# first.net
KiCad netlist of a schematic drawn in EAGLE
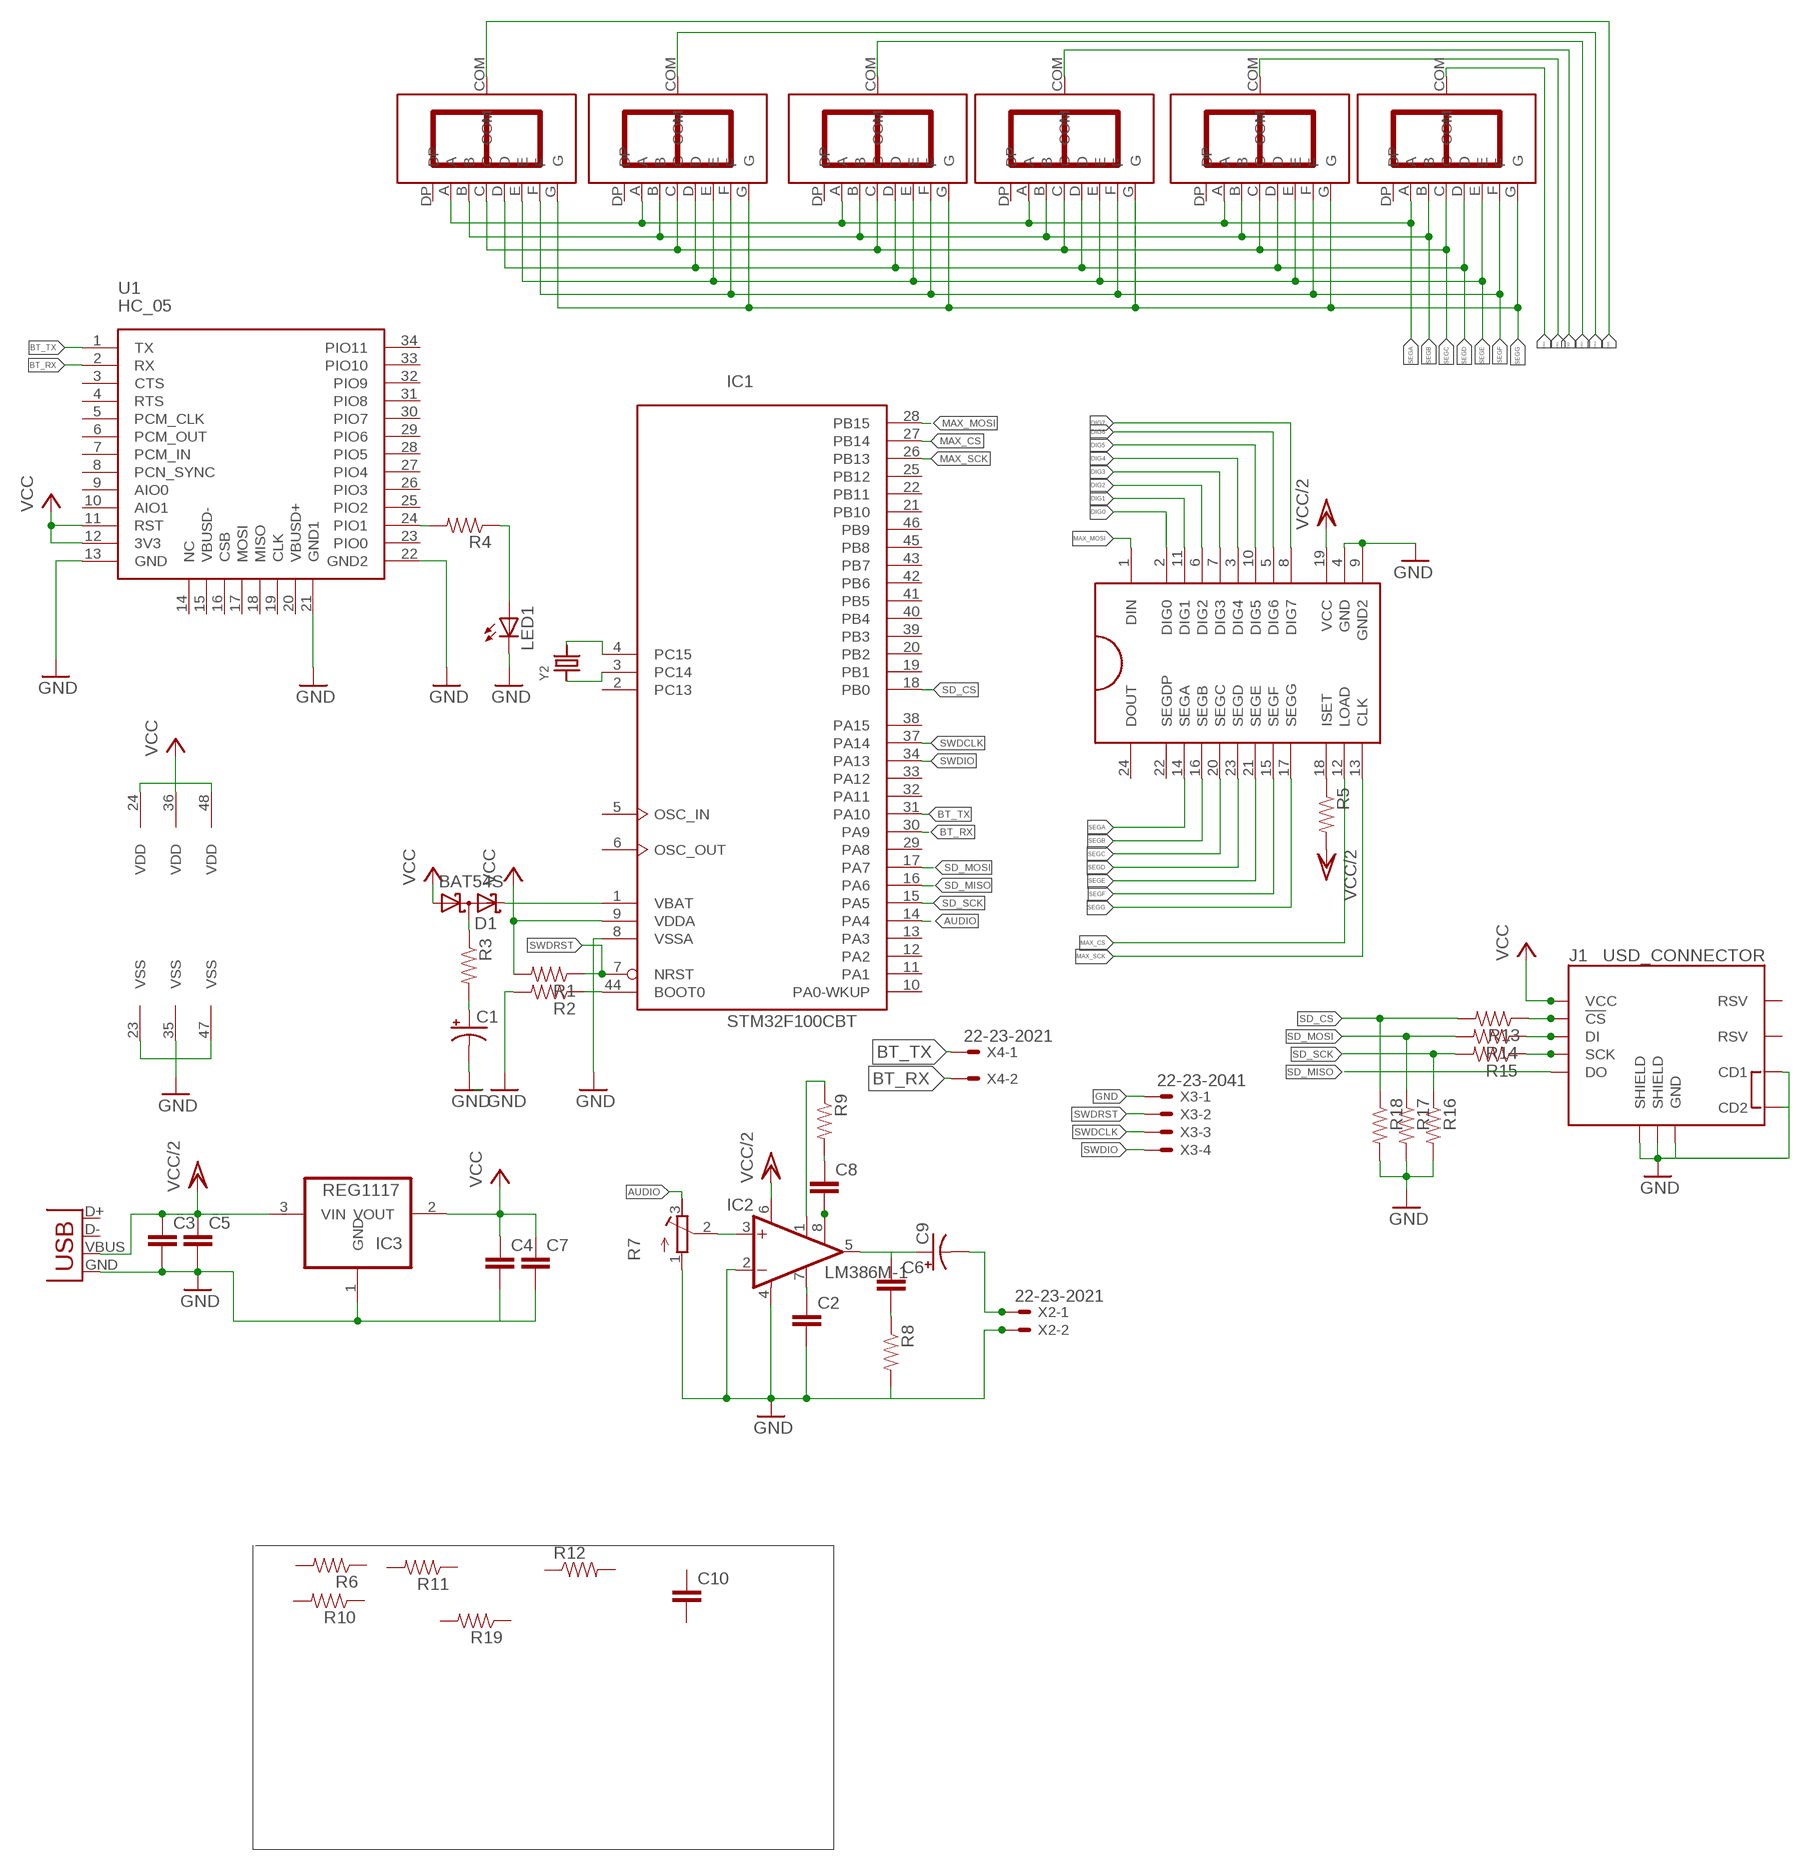
[diagram p0: schematic, sheet 1]

(export (version "E")
  (design (tool "Eeschema 10.0.6"))
  (components
    (comp (ref "C1")
      (value "CAP_POLPTH2")
      (footprint "eagle-import:CPOL-RADIAL-10UF-25V")
      (libsource (lib "eagle-import") (part "SparkFun-Passives_CAP_POLPTH2"))
    )
    (comp (ref "C2")
      (value "C-EUC0805K")
      (footprint "eagle-import:C0805K")
      (libsource (lib "eagle-import") (part "C-EUC0805K"))
    )
    (comp (ref "C3")
      (value "C-EUC0805K")
      (footprint "eagle-import:C0805K")
      (libsource (lib "eagle-import") (part "C-EUC0805K"))
    )
    (comp (ref "C4")
      (value "C-EUC0805K")
      (footprint "eagle-import:C0805K")
      (libsource (lib "eagle-import") (part "C-EUC0805K"))
    )
    (comp (ref "C5")
      (value "C-EUC0805K")
      (footprint "eagle-import:C0805K")
      (libsource (lib "eagle-import") (part "C-EUC0805K"))
    )
    (comp (ref "C6")
      (value "C-EUC0805K")
      (footprint "eagle-import:C0805K")
      (libsource (lib "eagle-import") (part "C-EUC0805K"))
    )
    (comp (ref "C7")
      (value "C-EUC0805K")
      (footprint "eagle-import:C0805K")
      (libsource (lib "eagle-import") (part "C-EUC0805K"))
    )
    (comp (ref "C8")
      (value "C-EUC0805K")
      (footprint "eagle-import:C0805K")
      (libsource (lib "eagle-import") (part "C-EUC0805K"))
    )
    (comp (ref "C9")
      (value "CAP_POLD")
      (footprint "eagle-import:PANASONIC_D")
      (libsource (lib "eagle-import") (part "CAP_POLD"))
    )
    (comp (ref "C10")
      (value "CAP0402-CAP")
      (footprint "eagle-import:0402-CAP")
      (libsource (lib "eagle-import") (part "CAP0402-CAP"))
    )
    (comp (ref "D1")
      (value "BAT54S")
      (footprint "eagle-import:SOT23")
      (libsource (lib "eagle-import") (part "BAT54S"))
    )
    (comp (ref "IC1")
      (value "STM32F100CBT")
      (footprint "eagle-import:LQFP48")
      (libsource (lib "eagle-import") (part "STM32F100CTB"))
    )
    (comp (ref "IC2")
      (value "LM386M-1")
      (footprint "eagle-import:SO08")
      (libsource (lib "eagle-import") (part "LM386?-M1"))
    )
    (comp (ref "IC3")
      (value "REG1117")
      (footprint "eagle-import:SOT223")
      (libsource (lib "eagle-import") (part "REG1117"))
    )
    (comp (ref "J1")
      (value "USD_CONNECTOR")
      (footprint "eagle-import:MICRO-SD-SOCKET-PP")
      (libsource (lib "eagle-import") (part "USD_CONNECTOR"))
    )
    (comp (ref "LED1")
      (value "LEDCHIP-LED0805")
      (footprint "eagle-import:CHIP-LED0805")
      (libsource (lib "eagle-import") (part "LEDCHIP-LED0805"))
    )
    (comp (ref "R1")
      (value "RESISTOR0805-RES")
      (footprint "eagle-import:0805")
      (libsource (lib "eagle-import") (part "RESISTOR0805-RES"))
    )
    (comp (ref "R2")
      (value "RESISTOR0805-RES")
      (footprint "eagle-import:0805")
      (libsource (lib "eagle-import") (part "RESISTOR0805-RES"))
    )
    (comp (ref "R3")
      (value "RESISTOR0805-RES")
      (footprint "eagle-import:0805")
      (libsource (lib "eagle-import") (part "RESISTOR0805-RES"))
    )
    (comp (ref "R4")
      (value "RESISTOR0805-RES")
      (footprint "eagle-import:0805")
      (libsource (lib "eagle-import") (part "RESISTOR0805-RES"))
    )
    (comp (ref "R5")
      (value "RESISTOR0805-RES")
      (footprint "eagle-import:0805")
      (libsource (lib "eagle-import") (part "RESISTOR0805-RES"))
    )
    (comp (ref "R6")
      (value "RESISTOR0805-RES")
      (footprint "eagle-import:0805")
      (libsource (lib "eagle-import") (part "RESISTOR0805-RES"))
    )
    (comp (ref "R7")
      (value "R-TRIMM4G/J")
      (footprint "eagle-import:RTRIM4G_J")
      (libsource (lib "eagle-import") (part "R-TRIMM4G/J"))
    )
    (comp (ref "R8")
      (value "RESISTOR0805-RES")
      (footprint "eagle-import:0805")
      (libsource (lib "eagle-import") (part "RESISTOR0805-RES"))
    )
    (comp (ref "R9")
      (value "RESISTOR0805-RES")
      (footprint "eagle-import:0805")
      (libsource (lib "eagle-import") (part "RESISTOR0805-RES"))
    )
    (comp (ref "R10")
      (value "RESISTOR0805-RES")
      (footprint "eagle-import:0805")
      (libsource (lib "eagle-import") (part "RESISTOR0805-RES"))
    )
    (comp (ref "R11")
      (value "RESISTOR0805-RES")
      (footprint "eagle-import:0805")
      (libsource (lib "eagle-import") (part "RESISTOR0805-RES"))
    )
    (comp (ref "R12")
      (value "RESISTOR0402")
      (footprint "eagle-import:0402-RES")
      (libsource (lib "eagle-import") (part "RESISTOR0402"))
    )
    (comp (ref "R13")
      (value "RESISTOR0805-RES")
      (footprint "eagle-import:0805")
      (libsource (lib "eagle-import") (part "RESISTOR0805-RES"))
    )
    (comp (ref "R14")
      (value "RESISTOR0805-RES")
      (footprint "eagle-import:0805")
      (libsource (lib "eagle-import") (part "RESISTOR0805-RES"))
    )
    (comp (ref "R15")
      (value "RESISTOR0805-RES")
      (footprint "eagle-import:0805")
      (libsource (lib "eagle-import") (part "RESISTOR0805-RES"))
    )
    (comp (ref "R16")
      (value "RESISTOR0805-RES")
      (footprint "eagle-import:0805")
      (libsource (lib "eagle-import") (part "RESISTOR0805-RES"))
    )
    (comp (ref "R17")
      (value "RESISTOR0805-RES")
      (footprint "eagle-import:0805")
      (libsource (lib "eagle-import") (part "RESISTOR0805-RES"))
    )
    (comp (ref "R18")
      (value "RESISTOR0805-RES")
      (footprint "eagle-import:0805")
      (libsource (lib "eagle-import") (part "RESISTOR0805-RES"))
    )
    (comp (ref "R19")
      (value "RESISTOR0805-RES")
      (footprint "eagle-import:0805")
      (libsource (lib "eagle-import") (part "RESISTOR0805-RES"))
    )
    (comp (ref "U$2")
      (value "IV-9")
      (footprint "eagle-import:IV-9")
      (libsource (lib "eagle-import") (part "IV-9"))
    )
    (comp (ref "U$3")
      (value "IV-9")
      (footprint "eagle-import:IV-9")
      (libsource (lib "eagle-import") (part "IV-9"))
    )
    (comp (ref "U$4")
      (value "IV-9")
      (footprint "eagle-import:IV-9")
      (libsource (lib "eagle-import") (part "IV-9"))
    )
    (comp (ref "U$5")
      (value "IV-9")
      (footprint "eagle-import:IV-9")
      (libsource (lib "eagle-import") (part "IV-9"))
    )
    (comp (ref "U$6")
      (value "IV-9")
      (footprint "eagle-import:IV-9")
      (libsource (lib "eagle-import") (part "IV-9"))
    )
    (comp (ref "U$7")
      (value "IV-9")
      (footprint "eagle-import:IV-9")
      (libsource (lib "eagle-import") (part "IV-9"))
    )
    (comp (ref "U$8")
      (value "MAX7219SOIK42")
      (footprint "eagle-import:SO24L")
      (libsource (lib "eagle-import") (part "MAX7219SOIK42"))
    )
    (comp (ref "U1")
      (value "HC_05")
      (footprint "eagle-import:BLUETOOTH_SMD")
      (libsource (lib "eagle-import") (part "HC_05"))
    )
    (comp (ref "X1")
      (value "USBSMD")
      (footprint "eagle-import:USB-MINIB")
      (libsource (lib "eagle-import") (part "USBSMD"))
    )
    (comp (ref "X2")
      (value "22-23-2021")
      (footprint "eagle-import:22-23-2021")
      (fields (field (name "MF") "MOLEX"))
      (libsource (lib "eagle-import") (part "22-23-2021"))
    )
    (comp (ref "X3")
      (value "22-23-2041")
      (footprint "eagle-import:22-23-2041")
      (fields (field (name "MF") "MOLEX"))
      (libsource (lib "eagle-import") (part "22-23-2041"))
    )
    (comp (ref "X4")
      (value "22-23-2021")
      (footprint "eagle-import:22-23-2021")
      (fields (field (name "MF") "MOLEX"))
      (libsource (lib "eagle-import") (part "22-23-2021"))
    )
    (comp (ref "Y2")
      (value "CRYSTAL8X3.8SMT")
      (footprint "eagle-import:CRYSTAL_8X3.8")
      (libsource (lib "eagle-import") (part "CRYSTAL8X3.8SMT"))
    )
  )
  (nets
    (net (code "1") (name "AUDIO") (class "Default")
      (node (ref "IC1") (pin "14") (pinfunction "PA4_14") (pintype "bidirectional"))
      (node (ref "R7") (pin "3") (pinfunction "E_3") (pintype "passive"))
    )
    (net (code "2") (name "BT_RX") (class "Default")
      (node (ref "IC1") (pin "30") (pinfunction "PA9_30") (pintype "bidirectional"))
      (node (ref "U1") (pin "2") (pinfunction "RX_2") (pintype "bidirectional"))
      (node (ref "X4") (pin "2") (pinfunction "S_2") (pintype "passive"))
    )
    (net (code "3") (name "BT_TX") (class "Default")
      (node (ref "IC1") (pin "31") (pinfunction "PA10_31") (pintype "bidirectional"))
      (node (ref "U1") (pin "1") (pinfunction "TX_1") (pintype "bidirectional"))
      (node (ref "X4") (pin "1") (pinfunction "S_1") (pintype "passive"))
    )
    (net (code "4") (name "DIG0") (class "Default")
      (node (ref "U$7") (pin "COM") (pinfunction "COM_COM") (pintype "bidirectional"))
      (node (ref "U$8") (pin "2") (pinfunction "DIG0_2") (pintype "bidirectional"))
    )
    (net (code "5") (name "DIG1") (class "Default")
      (node (ref "U$6") (pin "COM") (pinfunction "COM_COM") (pintype "bidirectional"))
      (node (ref "U$8") (pin "11") (pinfunction "DIG1_11") (pintype "bidirectional"))
    )
    (net (code "6") (name "DIG2") (class "Default")
      (node (ref "U$5") (pin "COM") (pinfunction "COM_COM") (pintype "bidirectional"))
      (node (ref "U$8") (pin "6") (pinfunction "DIG2_6") (pintype "bidirectional"))
    )
    (net (code "7") (name "DIG3") (class "Default")
      (node (ref "U$4") (pin "COM") (pinfunction "COM_COM") (pintype "bidirectional"))
      (node (ref "U$8") (pin "7") (pinfunction "DIG3_7") (pintype "bidirectional"))
    )
    (net (code "8") (name "DIG4") (class "Default")
      (node (ref "U$3") (pin "COM") (pinfunction "COM_COM") (pintype "bidirectional"))
      (node (ref "U$8") (pin "3") (pinfunction "DIG4_3") (pintype "bidirectional"))
    )
    (net (code "9") (name "DIG5") (class "Default")
      (node (ref "U$2") (pin "COM") (pinfunction "COM_COM") (pintype "bidirectional"))
      (node (ref "U$8") (pin "10") (pinfunction "DIG5_10") (pintype "bidirectional"))
    )
    (net (code "10") (name "DIG6") (class "Default")
      (node (ref "U$8") (pin "5") (pinfunction "DIG6_5") (pintype "bidirectional"))
    )
    (net (code "11") (name "DIG7") (class "Default")
      (node (ref "U$8") (pin "8") (pinfunction "DIG7_8") (pintype "bidirectional"))
    )
    (net (code "12") (name "GND") (class "Default")
      (node (ref "C1") (pin "2") (pinfunction "-_2") (pintype "passive"))
      (node (ref "C2") (pin "2") (pinfunction "2_2") (pintype "passive"))
      (node (ref "C3") (pin "2") (pinfunction "2_2") (pintype "passive"))
      (node (ref "C4") (pin "2") (pinfunction "2_2") (pintype "passive"))
      (node (ref "C5") (pin "2") (pinfunction "2_2") (pintype "passive"))
      (node (ref "C7") (pin "2") (pinfunction "2_2") (pintype "passive"))
      (node (ref "IC1") (pin "23") (pinfunction "VSS_23") (pintype "power_in"))
      (node (ref "IC1") (pin "35") (pinfunction "VSS_35") (pintype "power_in"))
      (node (ref "IC1") (pin "47") (pinfunction "VSS_47") (pintype "power_in"))
      (node (ref "IC1") (pin "8") (pinfunction "VSSA_8") (pintype "power_in"))
      (node (ref "IC2") (pin "2") (pinfunction "-IN_2") (pintype "input"))
      (node (ref "IC2") (pin "4") (pinfunction "GND_4") (pintype "power_in"))
      (node (ref "IC3") (pin "1") (pinfunction "GND_1") (pintype "power_in"))
      (node (ref "J1") (pin "CD1") (pinfunction "CD1_CD1") (pintype "bidirectional"))
      (node (ref "J1") (pin "CD2") (pinfunction "CD2_CD2") (pintype "bidirectional"))
      (node (ref "J1") (pin "GND") (pinfunction "GND_GND") (pintype "bidirectional"))
      (node (ref "J1") (pin "GND1") (pinfunction "SHIELD_GND1") (pintype "bidirectional"))
      (node (ref "J1") (pin "GND3") (pinfunction "SHIELD_GND3") (pintype "bidirectional"))
      (node (ref "LED1") (pin "C") (pinfunction "C_C") (pintype "passive"))
      (node (ref "R16") (pin "2") (pinfunction "2_2") (pintype "passive"))
      (node (ref "R17") (pin "2") (pinfunction "2_2") (pintype "passive"))
      (node (ref "R18") (pin "2") (pinfunction "2_2") (pintype "passive"))
      (node (ref "R2") (pin "2") (pinfunction "2_2") (pintype "passive"))
      (node (ref "R7") (pin "1") (pinfunction "A_1") (pintype "passive"))
      (node (ref "R8") (pin "2") (pinfunction "2_2") (pintype "passive"))
      (node (ref "U$8") (pin "4") (pinfunction "GND_4") (pintype "bidirectional"))
      (node (ref "U$8") (pin "9") (pinfunction "GND2_9") (pintype "bidirectional"))
      (node (ref "U1") (pin "13") (pinfunction "GND_13") (pintype "bidirectional"))
      (node (ref "U1") (pin "21") (pinfunction "GND1_21") (pintype "bidirectional"))
      (node (ref "U1") (pin "22") (pinfunction "GND2_22") (pintype "bidirectional"))
      (node (ref "X1") (pin "GND") (pinfunction "GND_GND") (pintype "bidirectional"))
      (node (ref "X2") (pin "2") (pinfunction "S_2") (pintype "passive"))
      (node (ref "X3") (pin "1") (pinfunction "S_1") (pintype "passive"))
    )
    (net (code "13") (name "MAX_CS") (class "Default")
      (node (ref "IC1") (pin "27") (pinfunction "PB14_27") (pintype "bidirectional"))
      (node (ref "U$8") (pin "12") (pinfunction "LOAD_12") (pintype "bidirectional"))
    )
    (net (code "14") (name "MAX_MOSI") (class "Default")
      (node (ref "IC1") (pin "28") (pinfunction "PB15_28") (pintype "bidirectional"))
      (node (ref "U$8") (pin "1") (pinfunction "DIN_1") (pintype "bidirectional"))
    )
    (net (code "15") (name "MAX_SCK") (class "Default")
      (node (ref "IC1") (pin "26") (pinfunction "PB13_26") (pintype "bidirectional"))
      (node (ref "U$8") (pin "13") (pinfunction "CLK_13") (pintype "bidirectional"))
    )
    (net (code "16") (name "Net-(C1-+)") (class "Default")
      (node (ref "C1") (pin "1") (pinfunction "+_1") (pintype "passive"))
      (node (ref "R3") (pin "2") (pinfunction "2_2") (pintype "passive"))
    )
    (net (code "17") (name "Net-(C6-Pad2)") (class "Default")
      (node (ref "C6") (pin "2") (pinfunction "2_2") (pintype "passive"))
      (node (ref "R8") (pin "1") (pinfunction "1_1") (pintype "passive"))
    )
    (net (code "18") (name "Net-(C8-Pad1)") (class "Default")
      (node (ref "C8") (pin "1") (pinfunction "1_1") (pintype "passive"))
      (node (ref "R9") (pin "2") (pinfunction "2_2") (pintype "passive"))
    )
    (net (code "19") (name "Net-(C8-Pad2)") (class "Default")
      (node (ref "C8") (pin "2") (pinfunction "2_2") (pintype "passive"))
      (node (ref "IC2") (pin "8") (pinfunction "GAIN_8") (pintype "passive"))
    )
    (net (code "20") (name "Net-(D1-C1A2)") (class "Default")
      (node (ref "D1") (pin "3") (pinfunction "C1A2_3") (pintype "passive"))
      (node (ref "R3") (pin "1") (pinfunction "1_1") (pintype "passive"))
    )
    (net (code "21") (name "Net-(D1-C2)") (class "Default")
      (node (ref "D1") (pin "2") (pinfunction "C2_2") (pintype "passive"))
      (node (ref "IC1") (pin "1") (pinfunction "VBAT_1") (pintype "power_in"))
    )
    (net (code "22") (name "Net-(IC1A-BOOT0)") (class "Default")
      (node (ref "IC1") (pin "44") (pinfunction "BOOT0_44") (pintype "input"))
      (node (ref "R2") (pin "1") (pinfunction "1_1") (pintype "passive"))
    )
    (net (code "23") (name "Net-(IC1A-PC14)") (class "Default")
      (node (ref "IC1") (pin "3") (pinfunction "PC14_3") (pintype "bidirectional"))
      (node (ref "Y2") (pin "P$1") (pinfunction "1_P$1") (pintype "passive"))
    )
    (net (code "24") (name "Net-(IC1A-PC15)") (class "Default")
      (node (ref "IC1") (pin "4") (pinfunction "PC15_4") (pintype "bidirectional"))
      (node (ref "Y2") (pin "P$4") (pinfunction "2_P$4") (pintype "passive"))
    )
    (net (code "25") (name "Net-(IC2-+IN)") (class "Default")
      (node (ref "IC2") (pin "3") (pinfunction "+IN_3") (pintype "input"))
      (node (ref "R7") (pin "2") (pinfunction "S_2") (pintype "passive"))
    )
    (net (code "26") (name "Net-(IC2-BYPASS)") (class "Default")
      (node (ref "C2") (pin "1") (pinfunction "1_1") (pintype "passive"))
      (node (ref "IC2") (pin "7") (pinfunction "BYPASS_7") (pintype "passive"))
    )
    (net (code "27") (name "Net-(IC2-GAIN-Pad1)") (class "Default")
      (node (ref "IC2") (pin "1") (pinfunction "GAIN_1") (pintype "passive"))
      (node (ref "R9") (pin "1") (pinfunction "1_1") (pintype "passive"))
    )
    (net (code "28") (name "Net-(IC2-OUT)") (class "Default")
      (node (ref "C6") (pin "1") (pinfunction "1_1") (pintype "passive"))
      (node (ref "C9") (pin "+") (pinfunction "+_+") (pintype "passive"))
      (node (ref "IC2") (pin "5") (pinfunction "OUT_5") (pintype "output"))
    )
    (net (code "29") (name "Net-(J1-PadDI)") (class "Default")
      (node (ref "J1") (pin "DI") (pinfunction "DI_DI") (pintype "bidirectional"))
      (node (ref "R14") (pin "1") (pinfunction "1_1") (pintype "passive"))
    )
    (net (code "30") (name "Net-(J1-SCK)") (class "Default")
      (node (ref "J1") (pin "SCLK") (pinfunction "SCK_SCLK") (pintype "bidirectional"))
      (node (ref "R15") (pin "1") (pinfunction "1_1") (pintype "passive"))
    )
    (net (code "31") (name "Net-(J1-~{CS})") (class "Default")
      (node (ref "J1") (pin "CS") (pinfunction "~{CS}_CS") (pintype "bidirectional"))
      (node (ref "R13") (pin "1") (pinfunction "1_1") (pintype "passive"))
    )
    (net (code "32") (name "Net-(LED1-PadA)") (class "Default")
      (node (ref "LED1") (pin "A") (pinfunction "A_A") (pintype "passive"))
      (node (ref "R4") (pin "1") (pinfunction "1_1") (pintype "passive"))
    )
    (net (code "33") (name "Net-(U$8-ISET)") (class "Default")
      (node (ref "R5") (pin "1") (pinfunction "1_1") (pintype "passive"))
      (node (ref "U$8") (pin "18") (pinfunction "ISET_18") (pintype "bidirectional"))
    )
    (net (code "34") (name "Net-(U1-PIO1)") (class "Default")
      (node (ref "R4") (pin "2") (pinfunction "2_2") (pintype "passive"))
      (node (ref "U1") (pin "24") (pinfunction "PIO1_24") (pintype "bidirectional"))
    )
    (net (code "35") (name "Net-(X2A-S)") (class "Default")
      (node (ref "C9") (pin "-") (pinfunction "-_-") (pintype "passive"))
      (node (ref "X2") (pin "1") (pinfunction "S_1") (pintype "passive"))
    )
    (net (code "36") (name "SD_CS") (class "Default")
      (node (ref "IC1") (pin "18") (pinfunction "PB0_18") (pintype "bidirectional"))
      (node (ref "R13") (pin "2") (pinfunction "2_2") (pintype "passive"))
      (node (ref "R18") (pin "1") (pinfunction "1_1") (pintype "passive"))
    )
    (net (code "37") (name "SD_MISO") (class "Default")
      (node (ref "IC1") (pin "16") (pinfunction "PA6_16") (pintype "bidirectional"))
      (node (ref "J1") (pin "DO") (pinfunction "DO_DO") (pintype "bidirectional"))
    )
    (net (code "38") (name "SD_MOSI") (class "Default")
      (node (ref "IC1") (pin "17") (pinfunction "PA7_17") (pintype "bidirectional"))
      (node (ref "R14") (pin "2") (pinfunction "2_2") (pintype "passive"))
      (node (ref "R17") (pin "1") (pinfunction "1_1") (pintype "passive"))
    )
    (net (code "39") (name "SD_SCK") (class "Default")
      (node (ref "IC1") (pin "15") (pinfunction "PA5_15") (pintype "bidirectional"))
      (node (ref "R15") (pin "2") (pinfunction "2_2") (pintype "passive"))
      (node (ref "R16") (pin "1") (pinfunction "1_1") (pintype "passive"))
    )
    (net (code "40") (name "SEGA") (class "Default")
      (node (ref "U$2") (pin "A") (pinfunction "A_A") (pintype "bidirectional"))
      (node (ref "U$3") (pin "A") (pinfunction "A_A") (pintype "bidirectional"))
      (node (ref "U$4") (pin "A") (pinfunction "A_A") (pintype "bidirectional"))
      (node (ref "U$5") (pin "A") (pinfunction "A_A") (pintype "bidirectional"))
      (node (ref "U$6") (pin "A") (pinfunction "A_A") (pintype "bidirectional"))
      (node (ref "U$7") (pin "A") (pinfunction "A_A") (pintype "bidirectional"))
      (node (ref "U$8") (pin "14") (pinfunction "SEGA_14") (pintype "bidirectional"))
    )
    (net (code "41") (name "SEGB") (class "Default")
      (node (ref "U$2") (pin "B") (pinfunction "B_B") (pintype "bidirectional"))
      (node (ref "U$3") (pin "B") (pinfunction "B_B") (pintype "bidirectional"))
      (node (ref "U$4") (pin "B") (pinfunction "B_B") (pintype "bidirectional"))
      (node (ref "U$5") (pin "B") (pinfunction "B_B") (pintype "bidirectional"))
      (node (ref "U$6") (pin "B") (pinfunction "B_B") (pintype "bidirectional"))
      (node (ref "U$7") (pin "B") (pinfunction "B_B") (pintype "bidirectional"))
      (node (ref "U$8") (pin "16") (pinfunction "SEGB_16") (pintype "bidirectional"))
    )
    (net (code "42") (name "SEGC") (class "Default")
      (node (ref "U$2") (pin "C") (pinfunction "C_C") (pintype "bidirectional"))
      (node (ref "U$3") (pin "C") (pinfunction "C_C") (pintype "bidirectional"))
      (node (ref "U$4") (pin "C") (pinfunction "C_C") (pintype "bidirectional"))
      (node (ref "U$5") (pin "C") (pinfunction "C_C") (pintype "bidirectional"))
      (node (ref "U$6") (pin "C") (pinfunction "C_C") (pintype "bidirectional"))
      (node (ref "U$7") (pin "C") (pinfunction "C_C") (pintype "bidirectional"))
      (node (ref "U$8") (pin "20") (pinfunction "SEGC_20") (pintype "bidirectional"))
    )
    (net (code "43") (name "SEGD") (class "Default")
      (node (ref "U$2") (pin "D") (pinfunction "D_D") (pintype "bidirectional"))
      (node (ref "U$3") (pin "D") (pinfunction "D_D") (pintype "bidirectional"))
      (node (ref "U$4") (pin "D") (pinfunction "D_D") (pintype "bidirectional"))
      (node (ref "U$5") (pin "D") (pinfunction "D_D") (pintype "bidirectional"))
      (node (ref "U$6") (pin "D") (pinfunction "D_D") (pintype "bidirectional"))
      (node (ref "U$7") (pin "D") (pinfunction "D_D") (pintype "bidirectional"))
      (node (ref "U$8") (pin "23") (pinfunction "SEGD_23") (pintype "bidirectional"))
    )
    (net (code "44") (name "SEGE") (class "Default")
      (node (ref "U$2") (pin "E") (pinfunction "E_E") (pintype "bidirectional"))
      (node (ref "U$3") (pin "E") (pinfunction "E_E") (pintype "bidirectional"))
      (node (ref "U$4") (pin "E") (pinfunction "E_E") (pintype "bidirectional"))
      (node (ref "U$5") (pin "E") (pinfunction "E_E") (pintype "bidirectional"))
      (node (ref "U$6") (pin "E") (pinfunction "E_E") (pintype "bidirectional"))
      (node (ref "U$7") (pin "E") (pinfunction "E_E") (pintype "bidirectional"))
      (node (ref "U$8") (pin "21") (pinfunction "SEGE_21") (pintype "bidirectional"))
    )
    (net (code "45") (name "SEGF") (class "Default")
      (node (ref "U$2") (pin "F") (pinfunction "F_F") (pintype "bidirectional"))
      (node (ref "U$3") (pin "F") (pinfunction "F_F") (pintype "bidirectional"))
      (node (ref "U$4") (pin "F") (pinfunction "F_F") (pintype "bidirectional"))
      (node (ref "U$5") (pin "F") (pinfunction "F_F") (pintype "bidirectional"))
      (node (ref "U$6") (pin "F") (pinfunction "F_F") (pintype "bidirectional"))
      (node (ref "U$7") (pin "F") (pinfunction "F_F") (pintype "bidirectional"))
      (node (ref "U$8") (pin "15") (pinfunction "SEGF_15") (pintype "bidirectional"))
    )
    (net (code "46") (name "SEGG") (class "Default")
      (node (ref "U$2") (pin "G") (pinfunction "G_G") (pintype "bidirectional"))
      (node (ref "U$3") (pin "G") (pinfunction "G_G") (pintype "bidirectional"))
      (node (ref "U$4") (pin "G") (pinfunction "G_G") (pintype "bidirectional"))
      (node (ref "U$5") (pin "G") (pinfunction "G_G") (pintype "bidirectional"))
      (node (ref "U$6") (pin "G") (pinfunction "G_G") (pintype "bidirectional"))
      (node (ref "U$7") (pin "G") (pinfunction "G_G") (pintype "bidirectional"))
      (node (ref "U$8") (pin "17") (pinfunction "SEGG_17") (pintype "bidirectional"))
    )
    (net (code "47") (name "SWDCLK") (class "Default")
      (node (ref "IC1") (pin "37") (pinfunction "PA14_37") (pintype "bidirectional"))
      (node (ref "X3") (pin "3") (pinfunction "S_3") (pintype "passive"))
    )
    (net (code "48") (name "SWDIO") (class "Default")
      (node (ref "IC1") (pin "34") (pinfunction "PA13_34") (pintype "bidirectional"))
      (node (ref "X3") (pin "4") (pinfunction "S_4") (pintype "passive"))
    )
    (net (code "49") (name "SWDRST") (class "Default")
      (node (ref "IC1") (pin "7") (pinfunction "NRST_7") (pintype "bidirectional"))
      (node (ref "R1") (pin "1") (pinfunction "1_1") (pintype "passive"))
      (node (ref "X3") (pin "2") (pinfunction "S_2") (pintype "passive"))
    )
    (net (code "50") (name "VCC") (class "Default")
      (node (ref "C4") (pin "1") (pinfunction "1_1") (pintype "passive"))
      (node (ref "C7") (pin "1") (pinfunction "1_1") (pintype "passive"))
      (node (ref "D1") (pin "1") (pinfunction "A1_1") (pintype "passive"))
      (node (ref "IC1") (pin "24") (pinfunction "VDD_24") (pintype "power_in"))
      (node (ref "IC1") (pin "36") (pinfunction "VDD_36") (pintype "power_in"))
      (node (ref "IC1") (pin "48") (pinfunction "VDD_48") (pintype "power_in"))
      (node (ref "IC1") (pin "9") (pinfunction "VDDA_9") (pintype "power_in"))
      (node (ref "IC3") (pin "2") (pinfunction "VOUT_2") (pintype "output"))
      (node (ref "J1") (pin "VCC") (pinfunction "VCC_VCC") (pintype "bidirectional"))
      (node (ref "R1") (pin "2") (pinfunction "2_2") (pintype "passive"))
      (node (ref "U1") (pin "11") (pinfunction "RST_11") (pintype "bidirectional"))
      (node (ref "U1") (pin "12") (pinfunction "3V3_12") (pintype "bidirectional"))
    )
    (net (code "51") (name "VCC{slash}2") (class "Default")
      (node (ref "C3") (pin "1") (pinfunction "1_1") (pintype "passive"))
      (node (ref "C5") (pin "1") (pinfunction "1_1") (pintype "passive"))
      (node (ref "IC2") (pin "6") (pinfunction "VS_6") (pintype "power_in"))
      (node (ref "IC3") (pin "3") (pinfunction "VIN_3") (pintype "input"))
      (node (ref "R5") (pin "2") (pinfunction "2_2") (pintype "passive"))
      (node (ref "U$8") (pin "19") (pinfunction "VCC_19") (pintype "bidirectional"))
      (node (ref "X1") (pin "VBUS") (pinfunction "VBUS_VBUS") (pintype "bidirectional"))
    )
    (net (code "52") (name "unconnected-(C10-Pad1)") (class "Default")
      (node (ref "C10") (pin "1") (pinfunction "1_1") (pintype "passive"))
    )
    (net (code "53") (name "unconnected-(C10-Pad2)") (class "Default")
      (node (ref "C10") (pin "2") (pinfunction "2_2") (pintype "passive"))
    )
    (net (code "54") (name "unconnected-(IC1A-OSC_IN-Pad5)") (class "Default")
      (node (ref "IC1") (pin "5") (pinfunction "OSC_IN_5") (pintype "bidirectional"))
    )
    (net (code "55") (name "unconnected-(IC1A-OSC_OUT-Pad6)") (class "Default")
      (node (ref "IC1") (pin "6") (pinfunction "OSC_OUT_6") (pintype "bidirectional"))
    )
    (net (code "56") (name "unconnected-(IC1A-PA0-WKUP-Pad10)") (class "Default")
      (node (ref "IC1") (pin "10") (pinfunction "PA0-WKUP_10") (pintype "bidirectional"))
    )
    (net (code "57") (name "unconnected-(IC1A-PA1-Pad11)") (class "Default")
      (node (ref "IC1") (pin "11") (pinfunction "PA1_11") (pintype "bidirectional"))
    )
    (net (code "58") (name "unconnected-(IC1A-PA2-Pad12)") (class "Default")
      (node (ref "IC1") (pin "12") (pinfunction "PA2_12") (pintype "bidirectional"))
    )
    (net (code "59") (name "unconnected-(IC1A-PA3-Pad13)") (class "Default")
      (node (ref "IC1") (pin "13") (pinfunction "PA3_13") (pintype "bidirectional"))
    )
    (net (code "60") (name "unconnected-(IC1A-PA8-Pad29)") (class "Default")
      (node (ref "IC1") (pin "29") (pinfunction "PA8_29") (pintype "bidirectional"))
    )
    (net (code "61") (name "unconnected-(IC1A-PA11-Pad32)") (class "Default")
      (node (ref "IC1") (pin "32") (pinfunction "PA11_32") (pintype "bidirectional"))
    )
    (net (code "62") (name "unconnected-(IC1A-PA12-Pad33)") (class "Default")
      (node (ref "IC1") (pin "33") (pinfunction "PA12_33") (pintype "bidirectional"))
    )
    (net (code "63") (name "unconnected-(IC1A-PA15-Pad38)") (class "Default")
      (node (ref "IC1") (pin "38") (pinfunction "PA15_38") (pintype "bidirectional"))
    )
    (net (code "64") (name "unconnected-(IC1A-PB1-Pad19)") (class "Default")
      (node (ref "IC1") (pin "19") (pinfunction "PB1_19") (pintype "bidirectional"))
    )
    (net (code "65") (name "unconnected-(IC1A-PB2-Pad20)") (class "Default")
      (node (ref "IC1") (pin "20") (pinfunction "PB2_20") (pintype "bidirectional"))
    )
    (net (code "66") (name "unconnected-(IC1A-PB3-Pad39)") (class "Default")
      (node (ref "IC1") (pin "39") (pinfunction "PB3_39") (pintype "bidirectional"))
    )
    (net (code "67") (name "unconnected-(IC1A-PB4-Pad40)") (class "Default")
      (node (ref "IC1") (pin "40") (pinfunction "PB4_40") (pintype "bidirectional"))
    )
    (net (code "68") (name "unconnected-(IC1A-PB5-Pad41)") (class "Default")
      (node (ref "IC1") (pin "41") (pinfunction "PB5_41") (pintype "bidirectional"))
    )
    (net (code "69") (name "unconnected-(IC1A-PB6-Pad42)") (class "Default")
      (node (ref "IC1") (pin "42") (pinfunction "PB6_42") (pintype "bidirectional"))
    )
    (net (code "70") (name "unconnected-(IC1A-PB7-Pad43)") (class "Default")
      (node (ref "IC1") (pin "43") (pinfunction "PB7_43") (pintype "bidirectional"))
    )
    (net (code "71") (name "unconnected-(IC1A-PB8-Pad45)") (class "Default")
      (node (ref "IC1") (pin "45") (pinfunction "PB8_45") (pintype "bidirectional"))
    )
    (net (code "72") (name "unconnected-(IC1A-PB9-Pad46)") (class "Default")
      (node (ref "IC1") (pin "46") (pinfunction "PB9_46") (pintype "bidirectional"))
    )
    (net (code "73") (name "unconnected-(IC1A-PB10-Pad21)") (class "Default")
      (node (ref "IC1") (pin "21") (pinfunction "PB10_21") (pintype "bidirectional"))
    )
    (net (code "74") (name "unconnected-(IC1A-PB11-Pad22)") (class "Default")
      (node (ref "IC1") (pin "22") (pinfunction "PB11_22") (pintype "bidirectional"))
    )
    (net (code "75") (name "unconnected-(IC1A-PB12-Pad25)") (class "Default")
      (node (ref "IC1") (pin "25") (pinfunction "PB12_25") (pintype "bidirectional"))
    )
    (net (code "76") (name "unconnected-(IC1A-PC13-Pad2)") (class "Default")
      (node (ref "IC1") (pin "2") (pinfunction "PC13_2") (pintype "bidirectional"))
    )
    (net (code "77") (name "unconnected-(J1-RSV-PadRSV1)") (class "Default")
      (node (ref "J1") (pin "RSV1") (pinfunction "RSV_RSV1") (pintype "bidirectional"))
    )
    (net (code "78") (name "unconnected-(J1-RSV-PadRSV2)") (class "Default")
      (node (ref "J1") (pin "RSV2") (pinfunction "RSV_RSV2") (pintype "bidirectional"))
    )
    (net (code "79") (name "unconnected-(R6-Pad1)") (class "Default")
      (node (ref "R6") (pin "1") (pinfunction "1_1") (pintype "passive"))
    )
    (net (code "80") (name "unconnected-(R6-Pad2)") (class "Default")
      (node (ref "R6") (pin "2") (pinfunction "2_2") (pintype "passive"))
    )
    (net (code "81") (name "unconnected-(R10-Pad1)") (class "Default")
      (node (ref "R10") (pin "1") (pinfunction "1_1") (pintype "passive"))
    )
    (net (code "82") (name "unconnected-(R10-Pad2)") (class "Default")
      (node (ref "R10") (pin "2") (pinfunction "2_2") (pintype "passive"))
    )
    (net (code "83") (name "unconnected-(R11-Pad1)") (class "Default")
      (node (ref "R11") (pin "1") (pinfunction "1_1") (pintype "passive"))
    )
    (net (code "84") (name "unconnected-(R11-Pad2)") (class "Default")
      (node (ref "R11") (pin "2") (pinfunction "2_2") (pintype "passive"))
    )
    (net (code "85") (name "unconnected-(R12-Pad1)") (class "Default")
      (node (ref "R12") (pin "1") (pinfunction "1_1") (pintype "passive"))
    )
    (net (code "86") (name "unconnected-(R12-Pad2)") (class "Default")
      (node (ref "R12") (pin "2") (pinfunction "2_2") (pintype "passive"))
    )
    (net (code "87") (name "unconnected-(R19-Pad1)") (class "Default")
      (node (ref "R19") (pin "1") (pinfunction "1_1") (pintype "passive"))
    )
    (net (code "88") (name "unconnected-(R19-Pad2)") (class "Default")
      (node (ref "R19") (pin "2") (pinfunction "2_2") (pintype "passive"))
    )
    (net (code "89") (name "unconnected-(U$2-PadDP)") (class "Default")
      (node (ref "U$2") (pin "DP") (pinfunction "DP_DP") (pintype "bidirectional"))
    )
    (net (code "90") (name "unconnected-(U$3-PadDP)") (class "Default")
      (node (ref "U$3") (pin "DP") (pinfunction "DP_DP") (pintype "bidirectional"))
    )
    (net (code "91") (name "unconnected-(U$4-PadDP)") (class "Default")
      (node (ref "U$4") (pin "DP") (pinfunction "DP_DP") (pintype "bidirectional"))
    )
    (net (code "92") (name "unconnected-(U$5-PadDP)") (class "Default")
      (node (ref "U$5") (pin "DP") (pinfunction "DP_DP") (pintype "bidirectional"))
    )
    (net (code "93") (name "unconnected-(U$6-PadDP)") (class "Default")
      (node (ref "U$6") (pin "DP") (pinfunction "DP_DP") (pintype "bidirectional"))
    )
    (net (code "94") (name "unconnected-(U$7-PadDP)") (class "Default")
      (node (ref "U$7") (pin "DP") (pinfunction "DP_DP") (pintype "bidirectional"))
    )
    (net (code "95") (name "unconnected-(U$8-DOUT-Pad24)") (class "Default")
      (node (ref "U$8") (pin "24") (pinfunction "DOUT_24") (pintype "bidirectional"))
    )
    (net (code "96") (name "unconnected-(U$8-SEGDP-Pad22)") (class "Default")
      (node (ref "U$8") (pin "22") (pinfunction "SEGDP_22") (pintype "bidirectional"))
    )
    (net (code "97") (name "unconnected-(U1-AIO0-Pad9)") (class "Default")
      (node (ref "U1") (pin "9") (pinfunction "AIO0_9") (pintype "bidirectional"))
    )
    (net (code "98") (name "unconnected-(U1-AIO1-Pad10)") (class "Default")
      (node (ref "U1") (pin "10") (pinfunction "AIO1_10") (pintype "bidirectional"))
    )
    (net (code "99") (name "unconnected-(U1-CLK-Pad19)") (class "Default")
      (node (ref "U1") (pin "19") (pinfunction "CLK_19") (pintype "bidirectional"))
    )
    (net (code "100") (name "unconnected-(U1-CSB-Pad16)") (class "Default")
      (node (ref "U1") (pin "16") (pinfunction "CSB_16") (pintype "bidirectional"))
    )
    (net (code "101") (name "unconnected-(U1-CTS-Pad3)") (class "Default")
      (node (ref "U1") (pin "3") (pinfunction "CTS_3") (pintype "bidirectional"))
    )
    (net (code "102") (name "unconnected-(U1-MISO-Pad18)") (class "Default")
      (node (ref "U1") (pin "18") (pinfunction "MISO_18") (pintype "bidirectional"))
    )
    (net (code "103") (name "unconnected-(U1-MOSI-Pad17)") (class "Default")
      (node (ref "U1") (pin "17") (pinfunction "MOSI_17") (pintype "bidirectional"))
    )
    (net (code "104") (name "unconnected-(U1-NC-Pad14)") (class "Default")
      (node (ref "U1") (pin "14") (pinfunction "NC_14") (pintype "bidirectional"))
    )
    (net (code "105") (name "unconnected-(U1-PCM_CLK-Pad5)") (class "Default")
      (node (ref "U1") (pin "5") (pinfunction "PCM_CLK_5") (pintype "bidirectional"))
    )
    (net (code "106") (name "unconnected-(U1-PCM_IN-Pad7)") (class "Default")
      (node (ref "U1") (pin "7") (pinfunction "PCM_IN_7") (pintype "bidirectional"))
    )
    (net (code "107") (name "unconnected-(U1-PCM_OUT-Pad6)") (class "Default")
      (node (ref "U1") (pin "6") (pinfunction "PCM_OUT_6") (pintype "bidirectional"))
    )
    (net (code "108") (name "unconnected-(U1-PCN_SYNC-Pad8)") (class "Default")
      (node (ref "U1") (pin "8") (pinfunction "PCN_SYNC_8") (pintype "bidirectional"))
    )
    (net (code "109") (name "unconnected-(U1-PIO0-Pad23)") (class "Default")
      (node (ref "U1") (pin "23") (pinfunction "PIO0_23") (pintype "bidirectional"))
    )
    (net (code "110") (name "unconnected-(U1-PIO2-Pad25)") (class "Default")
      (node (ref "U1") (pin "25") (pinfunction "PIO2_25") (pintype "bidirectional"))
    )
    (net (code "111") (name "unconnected-(U1-PIO3-Pad26)") (class "Default")
      (node (ref "U1") (pin "26") (pinfunction "PIO3_26") (pintype "bidirectional"))
    )
    (net (code "112") (name "unconnected-(U1-PIO4-Pad27)") (class "Default")
      (node (ref "U1") (pin "27") (pinfunction "PIO4_27") (pintype "bidirectional"))
    )
    (net (code "113") (name "unconnected-(U1-PIO5-Pad28)") (class "Default")
      (node (ref "U1") (pin "28") (pinfunction "PIO5_28") (pintype "bidirectional"))
    )
    (net (code "114") (name "unconnected-(U1-PIO6-Pad29)") (class "Default")
      (node (ref "U1") (pin "29") (pinfunction "PIO6_29") (pintype "bidirectional"))
    )
    (net (code "115") (name "unconnected-(U1-PIO7-Pad30)") (class "Default")
      (node (ref "U1") (pin "30") (pinfunction "PIO7_30") (pintype "bidirectional"))
    )
    (net (code "116") (name "unconnected-(U1-PIO8-Pad31)") (class "Default")
      (node (ref "U1") (pin "31") (pinfunction "PIO8_31") (pintype "bidirectional"))
    )
    (net (code "117") (name "unconnected-(U1-PIO9-Pad32)") (class "Default")
      (node (ref "U1") (pin "32") (pinfunction "PIO9_32") (pintype "bidirectional"))
    )
    (net (code "118") (name "unconnected-(U1-PIO10-Pad33)") (class "Default")
      (node (ref "U1") (pin "33") (pinfunction "PIO10_33") (pintype "bidirectional"))
    )
    (net (code "119") (name "unconnected-(U1-PIO11-Pad34)") (class "Default")
      (node (ref "U1") (pin "34") (pinfunction "PIO11_34") (pintype "bidirectional"))
    )
    (net (code "120") (name "unconnected-(U1-RTS-Pad4)") (class "Default")
      (node (ref "U1") (pin "4") (pinfunction "RTS_4") (pintype "bidirectional"))
    )
    (net (code "121") (name "unconnected-(U1-VBUSD+-Pad20)") (class "Default")
      (node (ref "U1") (pin "20") (pinfunction "VBUSD+_20") (pintype "bidirectional"))
    )
    (net (code "122") (name "unconnected-(U1-VBUSD--Pad15)") (class "Default")
      (node (ref "U1") (pin "15") (pinfunction "VBUSD-_15") (pintype "bidirectional"))
    )
    (net (code "123") (name "unconnected-(X1-PadD+)") (class "Default")
      (node (ref "X1") (pin "D+") (pinfunction "D+_D+") (pintype "bidirectional"))
    )
    (net (code "124") (name "unconnected-(X1-PadD-)") (class "Default")
      (node (ref "X1") (pin "D-") (pinfunction "D-_D-") (pintype "bidirectional"))
    )
  )
)
